# MCU152A_AltRouting_Misc.net
KiCad netlist of a schematic drawn in Altium Designer
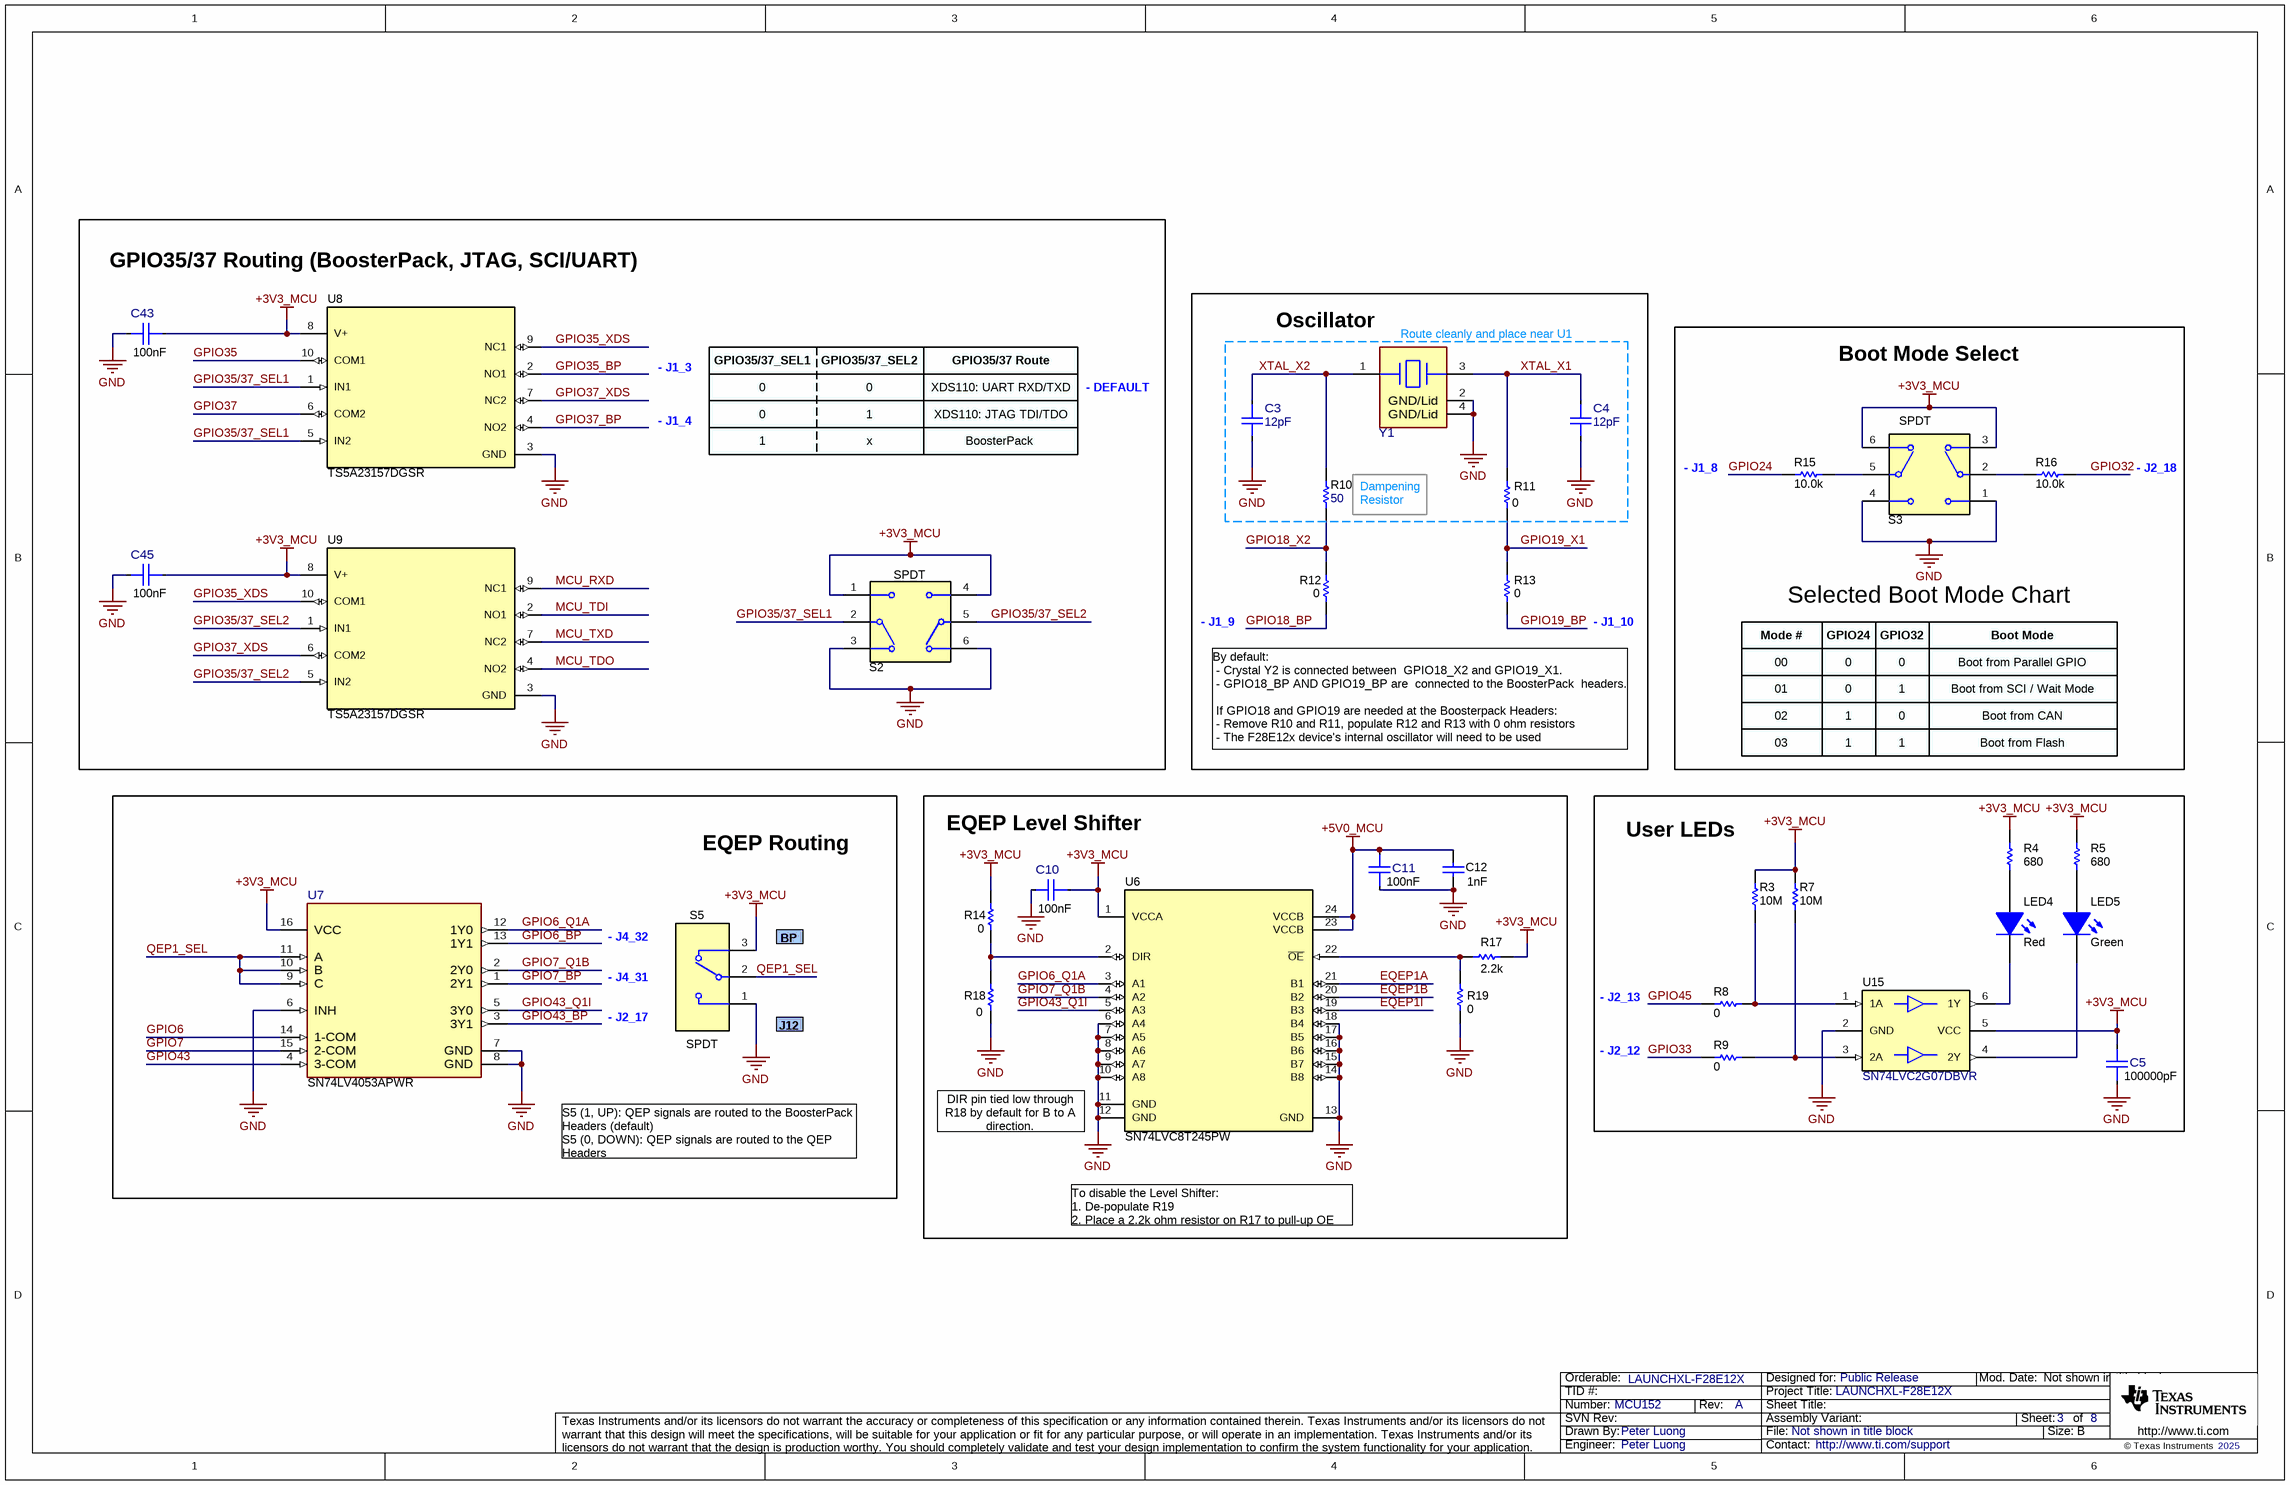
[diagram p0: MCU152A_AltRouting_Misc.SchDoc]

(export (version "E")
  (design (tool "Eeschema 10.0.6"))
  (components
    (comp (ref "C3")
      (value "885392005127")
      (footprint "FP-885392005127_0402-MFG")
      (description "12 pF ±2% 50V Ceramic Capacitor C0G, NP0 0402 (1005 Metric)")
      (fields
        (field (name "MANUFACTURER") "Wurth")
        (field (name "VALUEDISPLAYED") "12pF")
        (field (name "DIGIKEY PART NUMBER") "732-885392005127CT-ND")
      )
      (libsource (lib "Altium Vault - TI") (part "SYM-885392005127"))
    )
    (comp (ref "C4")
      (value "885392005127")
      (footprint "FP-885392005127_0402-MFG")
      (description "12 pF ±2% 50V Ceramic Capacitor C0G, NP0 0402 (1005 Metric)")
      (fields
        (field (name "MANUFACTURER") "Wurth")
        (field (name "VALUEDISPLAYED") "12pF")
        (field (name "DIGIKEY PART NUMBER") "732-885392005127CT-ND")
      )
      (libsource (lib "Altium Vault - TI") (part "SYM-885392005127"))
    )
    (comp (ref "C5")
      (value "885012205018")
      (footprint "FP-885012205018_0402-MFG")
      (description "0.1µF ±10% 10V Ceramic Capacitor X7R 0402 (1005 Metric)")
      (fields
        (field (name "MANUFACTURER") "Wurth Electronics")
        (field (name "MOUSER PART NUMBER") "710-885012205018")
        (field (name "VALUEDISPLAYED") "100000pF")
      )
      (libsource (lib "Altium Vault - TI") (part "SYM-885012205018"))
    )
    (comp (ref "C10")
      (value "885012205018")
      (footprint "FP-885012205018_0402-MFG")
      (description "0.1µF ±10% 10V Ceramic Capacitor X7R 0402 (1005 Metric)")
      (fields
        (field (name "MANUFACTURER") "Wurth Electronics")
        (field (name "MOUSER PART NUMBER") "710-885012205018")
        (field (name "CAP_F") "100nF")
      )
      (libsource (lib "Altium Vault - TI") (part "SYM-885012205018"))
    )
    (comp (ref "C11")
      (value "885012205018")
      (footprint "FP-885012205018_0402-MFG")
      (description "0.1µF ±10% 10V Ceramic Capacitor X7R 0402 (1005 Metric)")
      (fields
        (field (name "MANUFACTURER") "Wurth Electronics")
        (field (name "MOUSER PART NUMBER") "710-885012205018")
        (field (name "CAP_F") "100nF")
      )
      (libsource (lib "Altium Vault - TI") (part "SYM-885012205018"))
    )
    (comp (ref "C12")
      (value "885012205061")
      (footprint "0402")
      (description "CAP, CERM, 1000 pF, 50 V, +/- 10%, X7R, 0402")
      (fields
        (field (name "MANUFACTURER") "Wurth Elektronik")
        (field (name "CAP_F") "1nF")
        (field (name "PUBLISHER") "Texas Instruments")
      )
      (libsource (lib "Altium Vault - TI") (part "Capacitor"))
    )
    (comp (ref "C43")
      (value "885012205018")
      (footprint "FP-885012205018_0402-MFG")
      (description "0.1µF ±10% 10V Ceramic Capacitor X7R 0402 (1005 Metric)")
      (fields
        (field (name "MANUFACTURER") "Wurth Electronics")
        (field (name "MOUSER PART NUMBER") "710-885012205018")
        (field (name "CAP_F") "100nF")
      )
      (libsource (lib "Altium Vault - TI") (part "SYM-885012205018"))
    )
    (comp (ref "C45")
      (value "885012205018")
      (footprint "FP-885012205018_0402-MFG")
      (description "0.1µF ±10% 10V Ceramic Capacitor X7R 0402 (1005 Metric)")
      (fields
        (field (name "MANUFACTURER") "Wurth Electronics")
        (field (name "MOUSER PART NUMBER") "710-885012205018")
        (field (name "CAP_F") "100nF")
      )
      (libsource (lib "Altium Vault - TI") (part "SYM-885012205018"))
    )
    (comp (ref "LED4")
      (value "Red")
      (footprint "WL-SMCW_RED_0805")
      (description "LED, Red, SMD")
      (fields (field (name "MANUFACTURER") "Wurth Elektronik") (field (name "PARTNUMBER") "150080SS75000"))
      (libsource (lib "Altium Vault - TI") (part "LED_A2_K1"))
    )
    (comp (ref "LED5")
      (value "Green")
      (footprint "WL-SMCW_Green_0805")
      (description "LED, Green, SMD")
      (fields (field (name "PARTNUMBER") "150080GS75000") (field (name "MANUFACTURER") "Wurth Elektronik"))
      (libsource (lib "Altium Vault - TI") (part "LED_A2_K1"))
    )
    (comp (ref "R3")
      (value "CRCW040210M0JNED")
      (footprint "0402")
      (description "RES, 10 M, 5%, 0.063 W, AEC-Q200 Grade 0, 0402")
      (fields (field (name "VALUEDISPLAYED") "10M") (field (name "MANUFACTURER") "Vishay-Dale"))
      (libsource (lib "Altium Vault - TI") (part "Resistor"))
    )
    (comp (ref "R4")
      (value "CRCW0402680RJNED")
      (footprint "0402")
      (description "RES, 680, 5%, 0.063 W, AEC-Q200 Grade 0, 0402")
      (fields (field (name "MANUFACTURER") "Vishay-Dale") (field (name "VALUEDISPLAYED") "680"))
      (libsource (lib "Altium Vault - TI") (part "Resistor"))
    )
    (comp (ref "R5")
      (value "CRCW0402680RJNED")
      (footprint "0402")
      (description "RES, 680, 5%, 0.063 W, AEC-Q200 Grade 0, 0402")
      (fields (field (name "MANUFACTURER") "Vishay-Dale") (field (name "VALUEDISPLAYED") "680"))
      (libsource (lib "Altium Vault - TI") (part "Resistor"))
    )
    (comp (ref "R7")
      (value "CRCW040210M0JNED")
      (footprint "0402")
      (description "RES, 10 M, 5%, 0.063 W, AEC-Q200 Grade 0, 0402")
      (fields (field (name "VALUEDISPLAYED") "10M") (field (name "MANUFACTURER") "Vishay-Dale"))
      (libsource (lib "Altium Vault - TI") (part "Resistor"))
    )
    (comp (ref "R8")
      (value "CRCW06030000Z0EA")
      (footprint "0603")
      (description "RES, 0, 5%, 0.1 W, AEC-Q200 Grade 0, 0603")
      (fields (field (name "VALUEDISPLAYED") "0") (field (name "MANUFACTURER") "Vishay-Dale"))
      (libsource (lib "Altium Vault - TI") (part "Resistor"))
    )
    (comp (ref "R9")
      (value "CRCW06030000Z0EA")
      (footprint "0603")
      (description "RES, 0, 5%, 0.1 W, AEC-Q200 Grade 0, 0603")
      (fields (field (name "VALUEDISPLAYED") "0") (field (name "MANUFACTURER") "Vishay-Dale"))
      (libsource (lib "Altium Vault - TI") (part "Resistor"))
    )
    (comp (ref "R10")
      (value "FC0603E50R0BTBST1")
      (footprint "0603")
      (description "RES, 50, 0.1%, 0.125 W, 0603")
      (fields
        (field (name "MANUFACTURER") "Vishay Thin Film")
        (field (name "VALUEDISPLAYED") "50")
        (field (name "PUBLISHER") "Texas Instruments")
      )
      (libsource (lib "Altium Vault - TI") (part "Resistor"))
    )
    (comp (ref "R11")
      (value "CRCW06030000Z0EA")
      (footprint "0603")
      (description "RES, 0, 5%, 0.1 W, AEC-Q200 Grade 0, 0603")
      (fields (field (name "VALUEDISPLAYED") "0") (field (name "MANUFACTURER") "Vishay-Dale"))
      (libsource (lib "Altium Vault - TI") (part "Resistor"))
    )
    (comp (ref "R12")
      (value "CRCW06030000Z0EA")
      (footprint "0603")
      (description "RES, 0, 5%, 0.1 W, AEC-Q200 Grade 0, 0603")
      (fields (field (name "VALUEDISPLAYED") "0") (field (name "MANUFACTURER") "Vishay-Dale"))
      (libsource (lib "") (part "Resistor_1"))
    )
    (comp (ref "R13")
      (value "CRCW06030000Z0EA")
      (footprint "0603")
      (description "RES, 0, 5%, 0.1 W, AEC-Q200 Grade 0, 0603")
      (fields (field (name "VALUEDISPLAYED") "0") (field (name "MANUFACTURER") "Vishay-Dale"))
      (libsource (lib "Altium Vault - TI") (part "Resistor"))
    )
    (comp (ref "R14")
      (value "CRCW06030000Z0EA")
      (footprint "0603")
      (description "RES, 0, 5%, 0.1 W, AEC-Q200 Grade 0, 0603")
      (fields (field (name "VALUEDISPLAYED") "0") (field (name "MANUFACTURER") "Vishay-Dale"))
      (libsource (lib "Altium Vault - TI") (part "Resistor"))
    )
    (comp (ref "R15")
      (value "RC0603FR-0710KL")
      (footprint "0603")
      (description "RES, 10.0 k, 1%, 0.1 W, 0603")
      (fields (field (name "MANUFACTURER") "Yageo") (field (name "VALUEDISPLAYED") "10.0k"))
      (libsource (lib "Altium Vault - TI") (part "Resistor"))
    )
    (comp (ref "R16")
      (value "RC0603FR-0710KL")
      (footprint "0603")
      (description "RES, 10.0 k, 1%, 0.1 W, 0603")
      (fields (field (name "MANUFACTURER") "Yageo") (field (name "VALUEDISPLAYED") "10.0k"))
      (libsource (lib "Altium Vault - TI") (part "Resistor"))
    )
    (comp (ref "R17")
      (value "CRCW06032K20JNEA")
      (footprint "0603")
      (description "RES, 2.2 k, 5%, 0.1 W, AEC-Q200 Grade 0, 0603")
      (fields (field (name "VALUEDISPLAYED") "2.2k") (field (name "MANUFACTURER") "Vishay-Dale"))
      (libsource (lib "Altium Vault - TI") (part "Resistor"))
    )
    (comp (ref "R18")
      (value "CRCW06030000Z0EA")
      (footprint "0603")
      (description "RES, 0, 5%, 0.1 W, AEC-Q200 Grade 0, 0603")
      (fields (field (name "VALUEDISPLAYED") "0") (field (name "MANUFACTURER") "Vishay-Dale"))
      (libsource (lib "Altium Vault - TI") (part "Resistor"))
    )
    (comp (ref "R19")
      (value "CRCW06030000Z0EA")
      (footprint "0603")
      (description "RES, 0, 5%, 0.1 W, AEC-Q200 Grade 0, 0603")
      (fields (field (name "VALUEDISPLAYED") "0") (field (name "MANUFACTURER") "Vishay-Dale"))
      (libsource (lib "Altium Vault - TI") (part "Resistor"))
    )
    (comp (ref "S2")
      (value "CAS-D20TA")
      (footprint "SW_CAS-D20TA")
      (description "Switch, Dual SPDT,  2 Pos, 0.1A, 6VDC, SMD")
      (fields
        (field (name "MANUFACTURER") "Copal Electronics")
        (field (name "PUBLISHER") "Texas Instruments")
      )
      (libsource (lib "") (part "SW_SPDT_CAS-D20TA_1"))
    )
    (comp (ref "S3")
      (value "CAS-D20TA")
      (footprint "SW_CAS-D20TA")
      (description "Switch, Dual SPDT,  2 Pos, 0.1A, 6VDC, SMD")
      (fields
        (field (name "MANUFACTURER") "Copal Electronics")
        (field (name "PUBLISHER") "Texas Instruments")
      )
      (libsource (lib "Altium Vault - TI") (part "SW_SPDT_CAS-D20TA"))
    )
    (comp (ref "S5")
      (value "CAS-120TA")
      (footprint "SW_CAS-120TA")
      (description "Switch, Slide, SPDT  100mA, SMT")
      (fields
        (field (name "MANUFACTURER") "Copal Electronics")
        (field (name "PUBLISHER") "Texas Instruments")
      )
      (libsource (lib "Altium Vault - TI") (part "SW_CAS-120TA"))
    )
    (comp (ref "U6")
      (value "SN74LVC8T245PW")
      (footprint "PW0024A_N")
      (fields (field (name "MANUFACTURER") "Texas Instruments") (field (name "PARTNUMBER") "SN74LVC8T245PW"))
      (libsource (lib "Altium Vault - TI") (part "SN74LVC8T245"))
    )
    (comp (ref "U7")
      (value "SN74LV4053APWR")
      (footprint "PW0016A-MFG")
      (description "3 Circuit IC Switch 2:1 75Ohm 16-TSSOP")
      (fields
        (field (name "PARTNUMBER") "SN74LV4053APWR")
        (field (name "MOUSER PART NUMBER") "595-SN74LV4053APWR")
        (field (name "DIGIKEY PART NUMBER") "296-3833-1-ND")
      )
      (libsource (lib "Altium Vault - TI") (part "SYM-SN74LV4053APWR"))
    )
    (comp (ref "U8")
      (value "TS5A23157DGSR")
      (footprint "DGS0010A_N")
      (description "DUAL 10-Ohm SPDT ANALOG SWITCH, DGS0010A (VSSOP-10)")
      (fields
        (field (name "ALTERNATE PARTNUMBER") "TS5A23157DGST")
        (field (name "MANUFACTURER") "Texas Instruments")
        (field (name "PARTNUMBER") "TS5A23157DGSR")
        (field (name "PUBLISHER") "Texas Instruments")
      )
      (libsource (lib "Altium Vault - TI") (part "TS5A23159"))
    )
    (comp (ref "U9")
      (value "TS5A23157DGSR")
      (footprint "DGS0010A_N")
      (description "DUAL 10-Ohm SPDT ANALOG SWITCH, DGS0010A (VSSOP-10)")
      (fields
        (field (name "ALTERNATE PARTNUMBER") "TS5A23157DGST")
        (field (name "MANUFACTURER") "Texas Instruments")
        (field (name "PARTNUMBER") "TS5A23157DGSR")
        (field (name "PUBLISHER") "Texas Instruments")
      )
      (libsource (lib "Altium Vault - TI") (part "TS5A23159"))
    )
    (comp (ref "U15")
      (value "SN74LVC2G07DBVR")
      (footprint "DBV0006A_N")
      (description "Dual Buffer/Driver with Open-Drain Output, DBV0006A, LARGE T&R")
      (fields
        (field (name "GENERIC PART NUMBER") "SN74LVC2G07")
        (field (name "MANUFACTURER") "Texas Instruments")
      )
      (libsource (lib "Altium Vault - TI") (part "SN74LVC2G07"))
    )
    (comp (ref "Y1")
      (value "830108207209")
      (footprint "FP-830108207209_SMT_CRYSTAL_3MM2_2MM5-MFG")
      (description "20 MHz ±10ppm Crystal 8pF 50 Ohms 4-SMD, No Lead")
      (fields
        (field (name "DIGIKEY PART NUMBER") "1923-830108207209CT-ND")
        (field (name "MANUFACTURER") "Wurth Electronics")
      )
      (libsource (lib "Altium Vault - TI") (part "SYM-830108207209"))
    )
  )
  (nets
    (net (code "1") (name "+3V3_MCU") (class "Default")
      (node (ref "C10") (pin "1") (pinfunction "1_1") (pintype "passive"))
      (node (ref "C43") (pin "1") (pinfunction "1_1") (pintype "passive"))
      (node (ref "C45") (pin "1") (pinfunction "1_1") (pintype "passive"))
      (node (ref "C5") (pin "2") (pinfunction "2_2") (pintype "passive"))
      (node (ref "R14") (pin "2") (pinfunction "2_2") (pintype "passive"))
      (node (ref "R17") (pin "2") (pinfunction "2_2") (pintype "passive"))
      (node (ref "R3") (pin "2") (pinfunction "2_2") (pintype "passive"))
      (node (ref "R4") (pin "2") (pinfunction "2_2") (pintype "passive"))
      (node (ref "R5") (pin "2") (pinfunction "2_2") (pintype "passive"))
      (node (ref "R7") (pin "2") (pinfunction "2_2") (pintype "passive"))
      (node (ref "S2") (pin "1") (pinfunction "1_1") (pintype "passive"))
      (node (ref "S2") (pin "4") (pinfunction "4_4") (pintype "passive"))
      (node (ref "S3") (pin "3") (pinfunction "3_3") (pintype "passive"))
      (node (ref "S3") (pin "6") (pinfunction "6_6") (pintype "passive"))
      (node (ref "S5") (pin "3") (pinfunction "3_3") (pintype "passive"))
      (node (ref "U15") (pin "5") (pinfunction "VCC_5") (pintype "power_in"))
      (node (ref "U6") (pin "1") (pinfunction "VCCA_1") (pintype "power_in"))
      (node (ref "U7") (pin "16") (pinfunction "VCC_16") (pintype "power_in"))
      (node (ref "U8") (pin "8") (pinfunction "V+_8") (pintype "power_in"))
      (node (ref "U9") (pin "8") (pinfunction "V+_8") (pintype "power_in"))
    )
    (net (code "2") (name "+5V0_MCU") (class "Default")
      (node (ref "C11") (pin "2") (pinfunction "2_2") (pintype "passive"))
      (node (ref "C12") (pin "1") (pinfunction "1_1") (pintype "passive"))
      (node (ref "U6") (pin "23") (pinfunction "VCCB_23") (pintype "power_in"))
      (node (ref "U6") (pin "24") (pinfunction "VCCB_24") (pintype "power_in"))
    )
    (net (code "3") (name "/EQEP1A") (class "Default")
      (node (ref "U6") (pin "21") (pinfunction "B1_21") (pintype "bidirectional"))
    )
    (net (code "4") (name "/EQEP1B") (class "Default")
      (node (ref "U6") (pin "20") (pinfunction "B2_20") (pintype "bidirectional"))
    )
    (net (code "5") (name "/EQEP1I") (class "Default")
      (node (ref "U6") (pin "19") (pinfunction "B3_19") (pintype "bidirectional"))
    )
    (net (code "6") (name "/GPIO6") (class "Default")
      (node (ref "U7") (pin "14") (pinfunction "1-COM_14") (pintype "input"))
    )
    (net (code "7") (name "/GPIO6_BP") (class "Default")
      (node (ref "U7") (pin "13") (pinfunction "1Y1_13") (pintype "output"))
    )
    (net (code "8") (name "/GPIO6_Q1A") (class "Default")
      (node (ref "U6") (pin "3") (pinfunction "A1_3") (pintype "bidirectional"))
      (node (ref "U7") (pin "12") (pinfunction "1Y0_12") (pintype "output"))
    )
    (net (code "9") (name "/GPIO7") (class "Default")
      (node (ref "U7") (pin "15") (pinfunction "2-COM_15") (pintype "input"))
    )
    (net (code "10") (name "/GPIO7_BP") (class "Default")
      (node (ref "U7") (pin "1") (pinfunction "2Y1_1") (pintype "output"))
    )
    (net (code "11") (name "/GPIO7_Q1B") (class "Default")
      (node (ref "U6") (pin "4") (pinfunction "A2_4") (pintype "bidirectional"))
      (node (ref "U7") (pin "2") (pinfunction "2Y0_2") (pintype "output"))
    )
    (net (code "12") (name "/GPIO18_BP") (class "Default")
      (node (ref "R12") (pin "1") (pinfunction "1_1") (pintype "passive"))
    )
    (net (code "13") (name "/GPIO18_X2") (class "Default")
      (node (ref "R10") (pin "1") (pinfunction "1_1") (pintype "passive"))
      (node (ref "R12") (pin "2") (pinfunction "2_2") (pintype "passive"))
    )
    (net (code "14") (name "/GPIO19_BP") (class "Default")
      (node (ref "R13") (pin "1") (pinfunction "1_1") (pintype "passive"))
    )
    (net (code "15") (name "/GPIO19_X1") (class "Default")
      (node (ref "R11") (pin "1") (pinfunction "1_1") (pintype "passive"))
      (node (ref "R13") (pin "2") (pinfunction "2_2") (pintype "passive"))
    )
    (net (code "16") (name "/GPIO24") (class "Default")
      (node (ref "R15") (pin "1") (pinfunction "1_1") (pintype "passive"))
    )
    (net (code "17") (name "/GPIO32") (class "Default")
      (node (ref "R16") (pin "2") (pinfunction "2_2") (pintype "passive"))
    )
    (net (code "18") (name "/GPIO33") (class "Default")
      (node (ref "R9") (pin "1") (pinfunction "1_1") (pintype "passive"))
    )
    (net (code "19") (name "/GPIO35") (class "Default")
      (node (ref "U8") (pin "10") (pinfunction "COM1_10") (pintype "bidirectional"))
    )
    (net (code "20") (name "/GPIO35_BP") (class "Default")
      (node (ref "U8") (pin "2") (pinfunction "NO1_2") (pintype "bidirectional"))
    )
    (net (code "21") (name "/GPIO35_XDS") (class "Default")
      (node (ref "U8") (pin "9") (pinfunction "NC1_9") (pintype "bidirectional"))
      (node (ref "U9") (pin "10") (pinfunction "COM1_10") (pintype "bidirectional"))
    )
    (net (code "22") (name "/GPIO35{slash}37_SEL1") (class "Default")
      (node (ref "S2") (pin "2") (pinfunction "C_2") (pintype "passive"))
      (node (ref "U8") (pin "1") (pinfunction "IN1_1") (pintype "input"))
      (node (ref "U8") (pin "5") (pinfunction "IN2_5") (pintype "input"))
    )
    (net (code "23") (name "/GPIO35{slash}37_SEL2") (class "Default")
      (node (ref "S2") (pin "5") (pinfunction "C_5") (pintype "passive"))
      (node (ref "U9") (pin "1") (pinfunction "IN1_1") (pintype "input"))
      (node (ref "U9") (pin "5") (pinfunction "IN2_5") (pintype "input"))
    )
    (net (code "24") (name "/GPIO37") (class "Default")
      (node (ref "U8") (pin "6") (pinfunction "COM2_6") (pintype "bidirectional"))
    )
    (net (code "25") (name "/GPIO37_BP") (class "Default")
      (node (ref "U8") (pin "4") (pinfunction "NO2_4") (pintype "bidirectional"))
    )
    (net (code "26") (name "/GPIO37_XDS") (class "Default")
      (node (ref "U8") (pin "7") (pinfunction "NC2_7") (pintype "bidirectional"))
      (node (ref "U9") (pin "6") (pinfunction "COM2_6") (pintype "bidirectional"))
    )
    (net (code "27") (name "/GPIO43") (class "Default")
      (node (ref "U7") (pin "4") (pinfunction "3-COM_4") (pintype "input"))
    )
    (net (code "28") (name "/GPIO43_BP") (class "Default")
      (node (ref "U7") (pin "3") (pinfunction "3Y1_3") (pintype "output"))
    )
    (net (code "29") (name "/GPIO43_Q1I") (class "Default")
      (node (ref "U6") (pin "5") (pinfunction "A3_5") (pintype "bidirectional"))
      (node (ref "U7") (pin "5") (pinfunction "3Y0_5") (pintype "output"))
    )
    (net (code "30") (name "/GPIO45") (class "Default")
      (node (ref "R8") (pin "1") (pinfunction "1_1") (pintype "passive"))
    )
    (net (code "31") (name "/MCU_RXD") (class "Default")
      (node (ref "U9") (pin "9") (pinfunction "NC1_9") (pintype "bidirectional"))
    )
    (net (code "32") (name "/MCU_TDI") (class "Default")
      (node (ref "U9") (pin "2") (pinfunction "NO1_2") (pintype "bidirectional"))
    )
    (net (code "33") (name "/MCU_TDO") (class "Default")
      (node (ref "U9") (pin "4") (pinfunction "NO2_4") (pintype "bidirectional"))
    )
    (net (code "34") (name "/MCU_TXD") (class "Default")
      (node (ref "U9") (pin "7") (pinfunction "NC2_7") (pintype "bidirectional"))
    )
    (net (code "35") (name "/QEP1_SEL") (class "Default")
      (node (ref "S5") (pin "2") (pinfunction "2_2") (pintype "passive"))
      (node (ref "U7") (pin "10") (pinfunction "B_10") (pintype "input"))
      (node (ref "U7") (pin "11") (pinfunction "A_11") (pintype "input"))
      (node (ref "U7") (pin "9") (pinfunction "C_9") (pintype "input"))
    )
    (net (code "36") (name "/XTAL_X1") (class "Default")
      (node (ref "C4") (pin "1") (pinfunction "1_1") (pintype "passive"))
      (node (ref "R11") (pin "2") (pinfunction "2_2") (pintype "passive"))
      (node (ref "Y1") (pin "3") (pinfunction "2_Crystal_3") (pintype "passive"))
    )
    (net (code "37") (name "/XTAL_X2") (class "Default")
      (node (ref "C3") (pin "1") (pinfunction "1_1") (pintype "passive"))
      (node (ref "R10") (pin "2") (pinfunction "2_2") (pintype "passive"))
      (node (ref "Y1") (pin "1") (pinfunction "1_Crystal_1") (pintype "passive"))
    )
    (net (code "38") (name "GND") (class "Default")
      (node (ref "C10") (pin "2") (pinfunction "2_2") (pintype "passive"))
      (node (ref "C11") (pin "1") (pinfunction "1_1") (pintype "passive"))
      (node (ref "C12") (pin "2") (pinfunction "2_2") (pintype "passive"))
      (node (ref "C3") (pin "2") (pinfunction "2_2") (pintype "passive"))
      (node (ref "C4") (pin "2") (pinfunction "2_2") (pintype "passive"))
      (node (ref "C43") (pin "2") (pinfunction "2_2") (pintype "passive"))
      (node (ref "C45") (pin "2") (pinfunction "2_2") (pintype "passive"))
      (node (ref "C5") (pin "1") (pinfunction "1_1") (pintype "passive"))
      (node (ref "R18") (pin "1") (pinfunction "1_1") (pintype "passive"))
      (node (ref "R19") (pin "2") (pinfunction "2_2") (pintype "passive"))
      (node (ref "S2") (pin "3") (pinfunction "3_3") (pintype "passive"))
      (node (ref "S2") (pin "6") (pinfunction "6_6") (pintype "passive"))
      (node (ref "S3") (pin "1") (pinfunction "1_1") (pintype "passive"))
      (node (ref "S3") (pin "4") (pinfunction "4_4") (pintype "passive"))
      (node (ref "S5") (pin "1") (pinfunction "1_1") (pintype "passive"))
      (node (ref "U15") (pin "2") (pinfunction "GND_2") (pintype "power_in"))
      (node (ref "U6") (pin "10") (pinfunction "A8_10") (pintype "bidirectional"))
      (node (ref "U6") (pin "11") (pinfunction "GND_11") (pintype "power_in"))
      (node (ref "U6") (pin "12") (pinfunction "GND_12") (pintype "power_in"))
      (node (ref "U6") (pin "13") (pinfunction "GND_13") (pintype "power_in"))
      (node (ref "U6") (pin "14") (pinfunction "B8_14") (pintype "bidirectional"))
      (node (ref "U6") (pin "15") (pinfunction "B7_15") (pintype "bidirectional"))
      (node (ref "U6") (pin "16") (pinfunction "B6_16") (pintype "bidirectional"))
      (node (ref "U6") (pin "17") (pinfunction "B5_17") (pintype "bidirectional"))
      (node (ref "U6") (pin "18") (pinfunction "B4_18") (pintype "bidirectional"))
      (node (ref "U6") (pin "6") (pinfunction "A4_6") (pintype "bidirectional"))
      (node (ref "U6") (pin "7") (pinfunction "A5_7") (pintype "bidirectional"))
      (node (ref "U6") (pin "8") (pinfunction "A6_8") (pintype "bidirectional"))
      (node (ref "U6") (pin "9") (pinfunction "A7_9") (pintype "bidirectional"))
      (node (ref "U7") (pin "6") (pinfunction "INH_6") (pintype "input"))
      (node (ref "U7") (pin "7") (pinfunction "GND_7") (pintype "power_in"))
      (node (ref "U7") (pin "8") (pinfunction "GND_8") (pintype "power_in"))
      (node (ref "U8") (pin "3") (pinfunction "GND_3") (pintype "power_in"))
      (node (ref "U9") (pin "3") (pinfunction "GND_3") (pintype "power_in"))
      (node (ref "Y1") (pin "2") (pinfunction "GND/Lid_2") (pintype "power_in"))
      (node (ref "Y1") (pin "4") (pinfunction "GND/Lid_4") (pintype "power_in"))
    )
    (net (code "39") (name "Net-(LED4-A)") (class "Default")
      (node (ref "LED4") (pin "2") (pinfunction "A_2") (pintype "passive"))
      (node (ref "R4") (pin "1") (pinfunction "1_1") (pintype "passive"))
    )
    (net (code "40") (name "Net-(LED4-K)") (class "Default")
      (node (ref "LED4") (pin "1") (pinfunction "K_1") (pintype "passive"))
      (node (ref "U15") (pin "6") (pinfunction "1Y_6") (pintype "output"))
    )
    (net (code "41") (name "Net-(LED5-A)") (class "Default")
      (node (ref "LED5") (pin "2") (pinfunction "A_2") (pintype "passive"))
      (node (ref "R5") (pin "1") (pinfunction "1_1") (pintype "passive"))
    )
    (net (code "42") (name "Net-(LED5-K)") (class "Default")
      (node (ref "LED5") (pin "1") (pinfunction "K_1") (pintype "passive"))
      (node (ref "U15") (pin "4") (pinfunction "2Y_4") (pintype "output"))
    )
    (net (code "43") (name "Net-(R15-Pad2)") (class "Default")
      (node (ref "R15") (pin "2") (pinfunction "2_2") (pintype "passive"))
      (node (ref "S3") (pin "5") (pinfunction "C_5") (pintype "passive"))
    )
    (net (code "44") (name "Net-(R16-Pad1)") (class "Default")
      (node (ref "R16") (pin "1") (pinfunction "1_1") (pintype "passive"))
      (node (ref "S3") (pin "2") (pinfunction "C_2") (pintype "passive"))
    )
    (net (code "45") (name "Net-(U6-DIR)") (class "Default")
      (node (ref "R14") (pin "1") (pinfunction "1_1") (pintype "passive"))
      (node (ref "R18") (pin "2") (pinfunction "2_2") (pintype "passive"))
      (node (ref "U6") (pin "2") (pinfunction "DIR_2") (pintype "bidirectional"))
    )
    (net (code "46") (name "Net-(U6-OE)") (class "Default")
      (node (ref "R17") (pin "1") (pinfunction "1_1") (pintype "passive"))
      (node (ref "R19") (pin "1") (pinfunction "1_1") (pintype "passive"))
      (node (ref "U6") (pin "22") (pinfunction "OE_22") (pintype "input"))
    )
    (net (code "47") (name "Net-(U15-1A)") (class "Default")
      (node (ref "R3") (pin "1") (pinfunction "1_1") (pintype "passive"))
      (node (ref "R8") (pin "2") (pinfunction "2_2") (pintype "passive"))
      (node (ref "U15") (pin "1") (pinfunction "1A_1") (pintype "input"))
    )
    (net (code "48") (name "Net-(U15-2A)") (class "Default")
      (node (ref "R7") (pin "1") (pinfunction "1_1") (pintype "passive"))
      (node (ref "R9") (pin "2") (pinfunction "2_2") (pintype "passive"))
      (node (ref "U15") (pin "3") (pinfunction "2A_3") (pintype "input"))
    )
  )
)
